# 16_smd.net
KiCad netlist of a schematic drawn in EAGLE
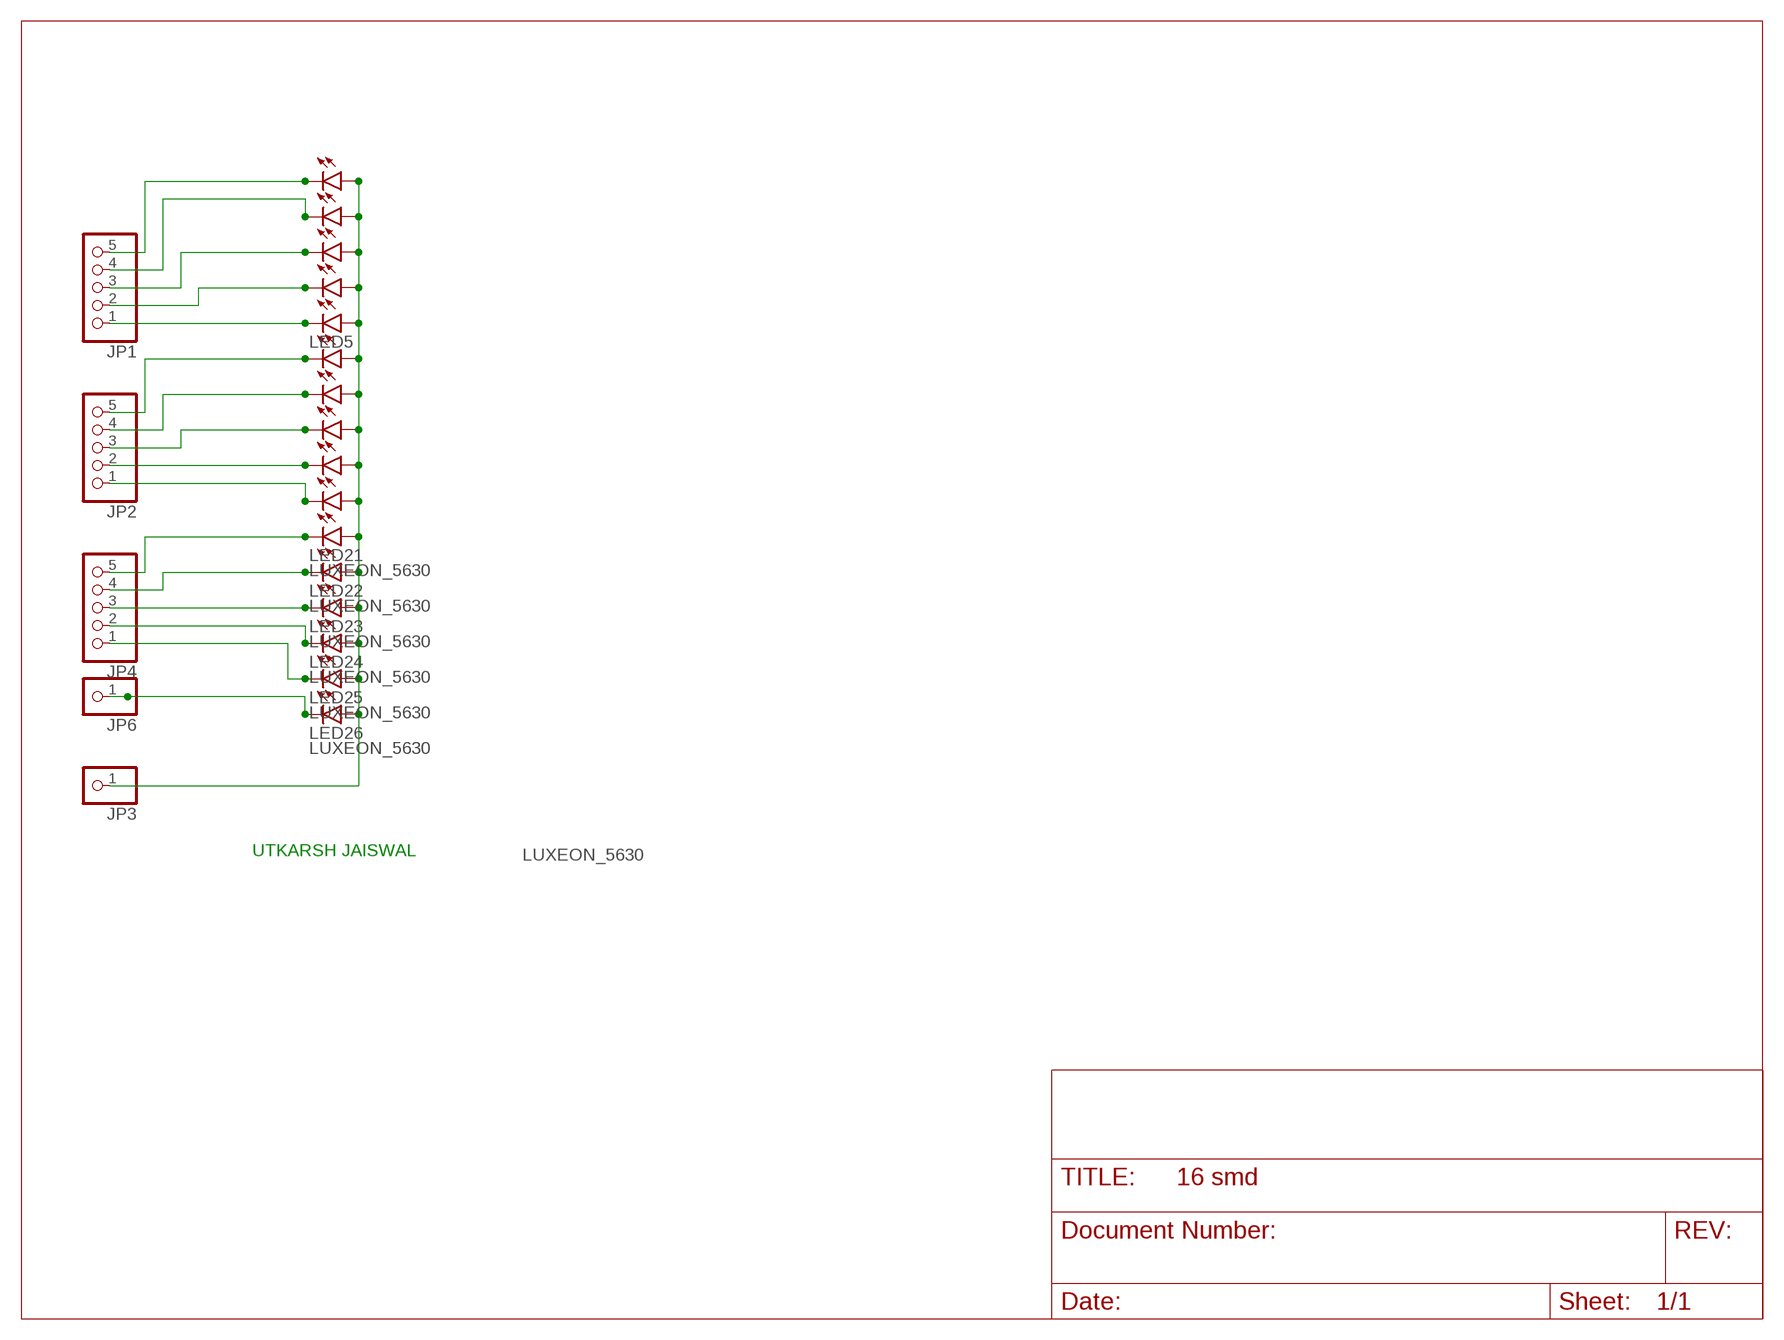
[diagram p0: schematic, sheet 1]

(export (version "E")
  (design (tool "Eeschema 10.0.6"))
  (components
    (comp (ref "JP1")
      (value "PINHD-1X5")
      (footprint "eagle-import:1X05")
      (libsource (lib "eagle-import") (part "PINHD-1X5"))
    )
    (comp (ref "JP2")
      (value "PINHD-1X5")
      (footprint "eagle-import:1X05")
      (libsource (lib "eagle-import") (part "PINHD-1X5"))
    )
    (comp (ref "JP3")
      (value "PINHD-1X1")
      (footprint "eagle-import:1X01")
      (libsource (lib "eagle-import") (part "PINHD-1X1"))
    )
    (comp (ref "JP4")
      (value "PINHD-1X5")
      (footprint "eagle-import:1X05")
      (libsource (lib "eagle-import") (part "PINHD-1X5"))
    )
    (comp (ref "JP6")
      (value "PINHD-1X1")
      (footprint "eagle-import:1X01")
      (libsource (lib "eagle-import") (part "PINHD-1X1"))
    )
    (comp (ref "LED1")
      (value "LUXEON_5630")
      (footprint "eagle-import:LUXEON_5630")
      (libsource (lib "eagle-import") (part "LUXEON_5630"))
    )
    (comp (ref "LED2")
      (value "LUXEON_5630")
      (footprint "eagle-import:LUXEON_5630")
      (libsource (lib "eagle-import") (part "LUXEON_5630"))
    )
    (comp (ref "LED3")
      (value "LUXEON_5630")
      (footprint "eagle-import:LUXEON_5630")
      (libsource (lib "eagle-import") (part "LUXEON_5630"))
    )
    (comp (ref "LED4")
      (value "LUXEON_5630")
      (footprint "eagle-import:LUXEON_5630")
      (libsource (lib "eagle-import") (part "LUXEON_5630"))
    )
    (comp (ref "LED5")
      (value "LUXEON_5630")
      (footprint "eagle-import:LUXEON_5630")
      (libsource (lib "eagle-import") (part "LUXEON_5630"))
    )
    (comp (ref "LED6")
      (value "LUXEON_5630")
      (footprint "eagle-import:LUXEON_5630")
      (libsource (lib "eagle-import") (part "LUXEON_5630"))
    )
    (comp (ref "LED7")
      (value "LUXEON_5630")
      (footprint "eagle-import:LUXEON_5630")
      (libsource (lib "eagle-import") (part "LUXEON_5630"))
    )
    (comp (ref "LED8")
      (value "LUXEON_5630")
      (footprint "eagle-import:LUXEON_5630")
      (libsource (lib "eagle-import") (part "LUXEON_5630"))
    )
    (comp (ref "LED9")
      (value "LUXEON_5630")
      (footprint "eagle-import:LUXEON_5630")
      (libsource (lib "eagle-import") (part "LUXEON_5630"))
    )
    (comp (ref "LED10")
      (value "LUXEON_5630")
      (footprint "eagle-import:LUXEON_5630")
      (libsource (lib "eagle-import") (part "LUXEON_5630"))
    )
    (comp (ref "LED21")
      (value "LUXEON_5630")
      (footprint "eagle-import:LUXEON_5630")
      (libsource (lib "eagle-import") (part "LUXEON_5630"))
    )
    (comp (ref "LED22")
      (value "LUXEON_5630")
      (footprint "eagle-import:LUXEON_5630")
      (libsource (lib "eagle-import") (part "LUXEON_5630"))
    )
    (comp (ref "LED23")
      (value "LUXEON_5630")
      (footprint "eagle-import:LUXEON_5630")
      (libsource (lib "eagle-import") (part "LUXEON_5630"))
    )
    (comp (ref "LED24")
      (value "LUXEON_5630")
      (footprint "eagle-import:LUXEON_5630")
      (libsource (lib "eagle-import") (part "LUXEON_5630"))
    )
    (comp (ref "LED25")
      (value "LUXEON_5630")
      (footprint "eagle-import:LUXEON_5630")
      (libsource (lib "eagle-import") (part "LUXEON_5630"))
    )
    (comp (ref "LED26")
      (value "LUXEON_5630")
      (footprint "eagle-import:LUXEON_5630")
      (libsource (lib "eagle-import") (part "LUXEON_5630"))
    )
  )
  (nets
    (net (code "1") (name "Net-(JP1-Pad1)") (class "Default")
      (node (ref "JP1") (pin "1") (pinfunction "1_1") (pintype "passive"))
      (node (ref "LED5") (pin "1@1") (pinfunction "C_1@1") (pintype "passive"))
      (node (ref "LED5") (pin "1@2") (pinfunction "C_1@2") (pintype "passive"))
    )
    (net (code "2") (name "Net-(JP1-Pad2)") (class "Default")
      (node (ref "JP1") (pin "2") (pinfunction "2_2") (pintype "passive"))
      (node (ref "LED4") (pin "1@1") (pinfunction "C_1@1") (pintype "passive"))
      (node (ref "LED4") (pin "1@2") (pinfunction "C_1@2") (pintype "passive"))
    )
    (net (code "3") (name "Net-(JP1-Pad3)") (class "Default")
      (node (ref "JP1") (pin "3") (pinfunction "3_3") (pintype "passive"))
      (node (ref "LED3") (pin "1@1") (pinfunction "C_1@1") (pintype "passive"))
      (node (ref "LED3") (pin "1@2") (pinfunction "C_1@2") (pintype "passive"))
    )
    (net (code "4") (name "Net-(JP1-Pad4)") (class "Default")
      (node (ref "JP1") (pin "4") (pinfunction "4_4") (pintype "passive"))
      (node (ref "LED2") (pin "1@1") (pinfunction "C_1@1") (pintype "passive"))
      (node (ref "LED2") (pin "1@2") (pinfunction "C_1@2") (pintype "passive"))
    )
    (net (code "5") (name "Net-(JP1-Pad5)") (class "Default")
      (node (ref "JP1") (pin "5") (pinfunction "5_5") (pintype "passive"))
      (node (ref "LED1") (pin "1@1") (pinfunction "C_1@1") (pintype "passive"))
      (node (ref "LED1") (pin "1@2") (pinfunction "C_1@2") (pintype "passive"))
    )
    (net (code "6") (name "Net-(JP2-Pad1)") (class "Default")
      (node (ref "JP2") (pin "1") (pinfunction "1_1") (pintype "passive"))
      (node (ref "LED10") (pin "1@1") (pinfunction "C_1@1") (pintype "passive"))
      (node (ref "LED10") (pin "1@2") (pinfunction "C_1@2") (pintype "passive"))
    )
    (net (code "7") (name "Net-(JP2-Pad2)") (class "Default")
      (node (ref "JP2") (pin "2") (pinfunction "2_2") (pintype "passive"))
      (node (ref "LED9") (pin "1@1") (pinfunction "C_1@1") (pintype "passive"))
      (node (ref "LED9") (pin "1@2") (pinfunction "C_1@2") (pintype "passive"))
    )
    (net (code "8") (name "Net-(JP2-Pad3)") (class "Default")
      (node (ref "JP2") (pin "3") (pinfunction "3_3") (pintype "passive"))
      (node (ref "LED8") (pin "1@1") (pinfunction "C_1@1") (pintype "passive"))
      (node (ref "LED8") (pin "1@2") (pinfunction "C_1@2") (pintype "passive"))
    )
    (net (code "9") (name "Net-(JP2-Pad4)") (class "Default")
      (node (ref "JP2") (pin "4") (pinfunction "4_4") (pintype "passive"))
      (node (ref "LED7") (pin "1@1") (pinfunction "C_1@1") (pintype "passive"))
      (node (ref "LED7") (pin "1@2") (pinfunction "C_1@2") (pintype "passive"))
    )
    (net (code "10") (name "Net-(JP2-Pad5)") (class "Default")
      (node (ref "JP2") (pin "5") (pinfunction "5_5") (pintype "passive"))
      (node (ref "LED6") (pin "1@1") (pinfunction "C_1@1") (pintype "passive"))
      (node (ref "LED6") (pin "1@2") (pinfunction "C_1@2") (pintype "passive"))
    )
    (net (code "11") (name "Net-(JP4-Pad1)") (class "Default")
      (node (ref "JP4") (pin "1") (pinfunction "1_1") (pintype "passive"))
      (node (ref "LED25") (pin "1@1") (pinfunction "C_1@1") (pintype "passive"))
      (node (ref "LED25") (pin "1@2") (pinfunction "C_1@2") (pintype "passive"))
    )
    (net (code "12") (name "Net-(JP4-Pad2)") (class "Default")
      (node (ref "JP4") (pin "2") (pinfunction "2_2") (pintype "passive"))
      (node (ref "LED24") (pin "1@1") (pinfunction "C_1@1") (pintype "passive"))
      (node (ref "LED24") (pin "1@2") (pinfunction "C_1@2") (pintype "passive"))
    )
    (net (code "13") (name "Net-(JP4-Pad3)") (class "Default")
      (node (ref "JP4") (pin "3") (pinfunction "3_3") (pintype "passive"))
      (node (ref "LED23") (pin "1@1") (pinfunction "C_1@1") (pintype "passive"))
      (node (ref "LED23") (pin "1@2") (pinfunction "C_1@2") (pintype "passive"))
    )
    (net (code "14") (name "Net-(JP4-Pad4)") (class "Default")
      (node (ref "JP4") (pin "4") (pinfunction "4_4") (pintype "passive"))
      (node (ref "LED22") (pin "1@1") (pinfunction "C_1@1") (pintype "passive"))
      (node (ref "LED22") (pin "1@2") (pinfunction "C_1@2") (pintype "passive"))
    )
    (net (code "15") (name "Net-(JP4-Pad5)") (class "Default")
      (node (ref "JP4") (pin "5") (pinfunction "5_5") (pintype "passive"))
      (node (ref "LED21") (pin "1@1") (pinfunction "C_1@1") (pintype "passive"))
      (node (ref "LED21") (pin "1@2") (pinfunction "C_1@2") (pintype "passive"))
    )
    (net (code "16") (name "Net-(JP6-Pad1)") (class "Default")
      (node (ref "JP6") (pin "1") (pinfunction "1_1") (pintype "passive"))
      (node (ref "LED26") (pin "1@1") (pinfunction "C_1@1") (pintype "passive"))
      (node (ref "LED26") (pin "1@2") (pinfunction "C_1@2") (pintype "passive"))
    )
    (net (code "17") (name "Net-(LED1-A)") (class "Default")
      (node (ref "JP3") (pin "1") (pinfunction "1_1") (pintype "passive"))
      (node (ref "LED1") (pin "2") (pinfunction "A_2") (pintype "passive"))
      (node (ref "LED10") (pin "2") (pinfunction "A_2") (pintype "passive"))
      (node (ref "LED2") (pin "2") (pinfunction "A_2") (pintype "passive"))
      (node (ref "LED21") (pin "2") (pinfunction "A_2") (pintype "passive"))
      (node (ref "LED22") (pin "2") (pinfunction "A_2") (pintype "passive"))
      (node (ref "LED23") (pin "2") (pinfunction "A_2") (pintype "passive"))
      (node (ref "LED24") (pin "2") (pinfunction "A_2") (pintype "passive"))
      (node (ref "LED25") (pin "2") (pinfunction "A_2") (pintype "passive"))
      (node (ref "LED26") (pin "2") (pinfunction "A_2") (pintype "passive"))
      (node (ref "LED3") (pin "2") (pinfunction "A_2") (pintype "passive"))
      (node (ref "LED4") (pin "2") (pinfunction "A_2") (pintype "passive"))
      (node (ref "LED5") (pin "2") (pinfunction "A_2") (pintype "passive"))
      (node (ref "LED6") (pin "2") (pinfunction "A_2") (pintype "passive"))
      (node (ref "LED7") (pin "2") (pinfunction "A_2") (pintype "passive"))
      (node (ref "LED8") (pin "2") (pinfunction "A_2") (pintype "passive"))
      (node (ref "LED9") (pin "2") (pinfunction "A_2") (pintype "passive"))
    )
  )
)
